# FT2232.net
KiCad netlist of a schematic drawn in Altium Designer
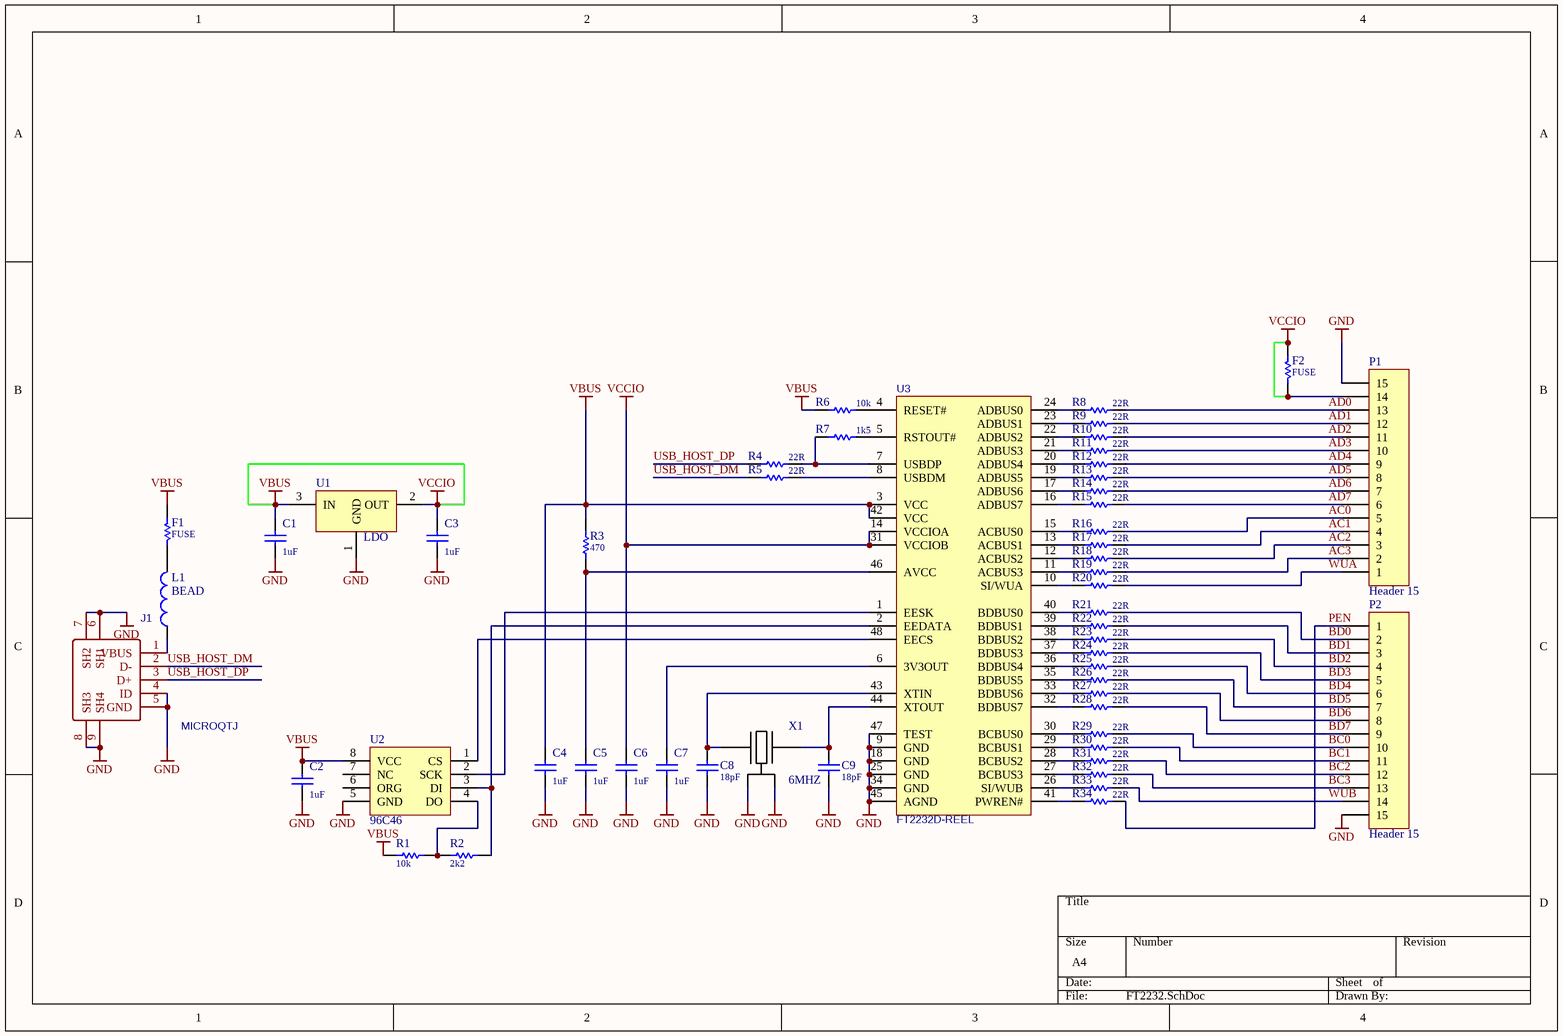
[diagram p0: FT2232.SchDoc]

(export (version "E")
  (design (tool "Eeschema 10.0.6"))
  (components
    (comp (ref "C1")
      (value "1uF")
      (footprint "C0603")
      (description "1uF 25V X7R 0603")
      (fields (field (name "LCSC PART NUMBER") "C59302"))
      (libsource (lib "Miscellaneous Devices") (part "CAP"))
    )
    (comp (ref "C2")
      (value "1uF")
      (footprint "C0603")
      (description "1uF 25V X7R 0603")
      (fields (field (name "LCSC PART NUMBER") "C59302"))
      (libsource (lib "Miscellaneous Devices") (part "CAP"))
    )
    (comp (ref "C3")
      (value "1uF")
      (footprint "C0603")
      (description "1uF 25V X7R 0603")
      (fields (field (name "LCSC PART NUMBER") "C59302"))
      (libsource (lib "Miscellaneous Devices") (part "CAP"))
    )
    (comp (ref "C4")
      (value "1uF")
      (footprint "C0603")
      (description "1uF 25V X7R 0603")
      (fields (field (name "LCSC PART NUMBER") "C59302"))
      (libsource (lib "Miscellaneous Devices") (part "CAP"))
    )
    (comp (ref "C5")
      (value "1uF")
      (footprint "C0603")
      (description "1uF 25V X7R 0603")
      (fields (field (name "LCSC PART NUMBER") "C59302"))
      (libsource (lib "Miscellaneous Devices") (part "CAP"))
    )
    (comp (ref "C6")
      (value "1uF")
      (footprint "C0603")
      (description "1uF 25V X7R 0603")
      (fields (field (name "LCSC PART NUMBER") "C59302"))
      (libsource (lib "Miscellaneous Devices") (part "CAP"))
    )
    (comp (ref "C7")
      (value "1uF")
      (footprint "C0603")
      (description "1uF 25V X7R 0603")
      (fields (field (name "LCSC PART NUMBER") "C59302"))
      (libsource (lib "Miscellaneous Devices") (part "CAP"))
    )
    (comp (ref "C8")
      (value "18pF")
      (footprint "C0402")
      (description "18pF 50V 0402")
      (fields (field (name "LCSC PART NUMBER") "C33149"))
      (libsource (lib "Miscellaneous Devices") (part "CAP"))
    )
    (comp (ref "C9")
      (value "18pF")
      (footprint "C0402")
      (description "18pF 50V 0402")
      (fields (field (name "LCSC PART NUMBER") "C33149"))
      (libsource (lib "Miscellaneous Devices") (part "CAP"))
    )
    (comp (ref "F1")
      (value "FUSE")
      (footprint "R1206")
      (libsource (lib "Miscellaneous Devices") (part "RES"))
    )
    (comp (ref "F2")
      (value "FUSE")
      (footprint "R1206")
      (libsource (lib "Miscellaneous Devices") (part "RES"))
    )
    (comp (ref "J1")
      (value "MICROQTJ")
      (footprint "MICRO-USB-SMD_MICROQTJ")
      (fields
        (field (name "BOM_SUPPLIER PART") "C404968")
        (field (name "BOM_MANUFACTURER PART") "MicroQTJ")
        (field (name "CONTRIBUTOR") "LCSC")
      )
      (libsource (lib "altium-import") (part "root_0_MICROQTJ_"))
    )
    (comp (ref "L1")
      (value "BEAD")
      (footprint "L0402")
      (description "INDUCTOR FERRITE BEAD 200mA 1 650mΩ 0402")
      (fields (field (name "LCSC PART NUMBER") "C92615"))
      (libsource (lib "Miscellaneous Devices") (part "BLM18AG601SN1D"))
    )
    (comp (ref "P1")
      (value "Header 15")
      (footprint "HDR1X15")
      (description "Header, 15-Pin")
      (fields (field (name "PUBLISHER") "Altium Limited"))
      (libsource (lib "Miscellaneous Connectors") (part "Header 15"))
    )
    (comp (ref "P2")
      (value "Header 15")
      (footprint "HDR1X15")
      (description "Header, 15-Pin")
      (fields (field (name "PUBLISHER") "Altium Limited"))
      (libsource (lib "") (part "Header 15_1"))
    )
    (comp (ref "R1")
      (value "10k")
      (footprint "R0603")
      (description "10k 0603")
      (libsource (lib "Miscellaneous Devices") (part "RES"))
    )
    (comp (ref "R2") (value "2k2") (footprint "R0603") (libsource (lib "Miscellaneous Devices") (part "RES")))
    (comp (ref "R3") (value "470") (footprint "R0603") (libsource (lib "Miscellaneous Devices") (part "RES")))
    (comp (ref "R4")
      (value "22R")
      (footprint "R0603")
      (description "22R 5% 0603")
      (libsource (lib "Miscellaneous Devices") (part "RES"))
    )
    (comp (ref "R5")
      (value "22R")
      (footprint "R0603")
      (description "22R 5% 0603")
      (libsource (lib "Miscellaneous Devices") (part "RES"))
    )
    (comp (ref "R6")
      (value "10k")
      (footprint "R0603")
      (description "10k 0603")
      (libsource (lib "Miscellaneous Devices") (part "RES"))
    )
    (comp (ref "R7")
      (value "1k5")
      (footprint "R0603")
      (description "10k 0603")
      (libsource (lib "Miscellaneous Devices") (part "RES"))
    )
    (comp (ref "R8")
      (value "22R")
      (footprint "R0603")
      (description "22R 5% 0603")
      (libsource (lib "Miscellaneous Devices") (part "RES"))
    )
    (comp (ref "R9")
      (value "22R")
      (footprint "R0603")
      (description "22R 5% 0603")
      (libsource (lib "Miscellaneous Devices") (part "RES"))
    )
    (comp (ref "R10")
      (value "22R")
      (footprint "R0603")
      (description "22R 5% 0603")
      (libsource (lib "Miscellaneous Devices") (part "RES"))
    )
    (comp (ref "R11")
      (value "22R")
      (footprint "R0603")
      (description "22R 5% 0603")
      (libsource (lib "Miscellaneous Devices") (part "RES"))
    )
    (comp (ref "R12")
      (value "22R")
      (footprint "R0603")
      (description "22R 5% 0603")
      (libsource (lib "Miscellaneous Devices") (part "RES"))
    )
    (comp (ref "R13")
      (value "22R")
      (footprint "R0603")
      (description "22R 5% 0603")
      (libsource (lib "Miscellaneous Devices") (part "RES"))
    )
    (comp (ref "R14")
      (value "22R")
      (footprint "R0603")
      (description "22R 5% 0603")
      (libsource (lib "Miscellaneous Devices") (part "RES"))
    )
    (comp (ref "R15")
      (value "22R")
      (footprint "R0603")
      (description "22R 5% 0603")
      (libsource (lib "Miscellaneous Devices") (part "RES"))
    )
    (comp (ref "R16")
      (value "22R")
      (footprint "R0603")
      (description "22R 5% 0603")
      (libsource (lib "Miscellaneous Devices") (part "RES"))
    )
    (comp (ref "R17")
      (value "22R")
      (footprint "R0603")
      (description "22R 5% 0603")
      (libsource (lib "Miscellaneous Devices") (part "RES"))
    )
    (comp (ref "R18")
      (value "22R")
      (footprint "R0603")
      (description "22R 5% 0603")
      (libsource (lib "Miscellaneous Devices") (part "RES"))
    )
    (comp (ref "R19")
      (value "22R")
      (footprint "R0603")
      (description "22R 5% 0603")
      (libsource (lib "Miscellaneous Devices") (part "RES"))
    )
    (comp (ref "R20")
      (value "22R")
      (footprint "R0603")
      (description "22R 5% 0603")
      (libsource (lib "Miscellaneous Devices") (part "RES"))
    )
    (comp (ref "R21")
      (value "22R")
      (footprint "R0603")
      (description "22R 5% 0603")
      (libsource (lib "Miscellaneous Devices") (part "RES"))
    )
    (comp (ref "R22")
      (value "22R")
      (footprint "R0603")
      (description "22R 5% 0603")
      (libsource (lib "Miscellaneous Devices") (part "RES"))
    )
    (comp (ref "R23")
      (value "22R")
      (footprint "R0603")
      (description "22R 5% 0603")
      (libsource (lib "Miscellaneous Devices") (part "RES"))
    )
    (comp (ref "R24")
      (value "22R")
      (footprint "R0603")
      (description "22R 5% 0603")
      (libsource (lib "Miscellaneous Devices") (part "RES"))
    )
    (comp (ref "R25")
      (value "22R")
      (footprint "R0603")
      (description "22R 5% 0603")
      (libsource (lib "Miscellaneous Devices") (part "RES"))
    )
    (comp (ref "R26")
      (value "22R")
      (footprint "R0603")
      (description "22R 5% 0603")
      (libsource (lib "Miscellaneous Devices") (part "RES"))
    )
    (comp (ref "R27")
      (value "22R")
      (footprint "R0603")
      (description "22R 5% 0603")
      (libsource (lib "Miscellaneous Devices") (part "RES"))
    )
    (comp (ref "R28")
      (value "22R")
      (footprint "R0603")
      (description "22R 5% 0603")
      (libsource (lib "Miscellaneous Devices") (part "RES"))
    )
    (comp (ref "R29")
      (value "22R")
      (footprint "R0603")
      (description "22R 5% 0603")
      (libsource (lib "Miscellaneous Devices") (part "RES"))
    )
    (comp (ref "R30")
      (value "22R")
      (footprint "R0603")
      (description "22R 5% 0603")
      (libsource (lib "Miscellaneous Devices") (part "RES"))
    )
    (comp (ref "R31")
      (value "22R")
      (footprint "R0603")
      (description "22R 5% 0603")
      (libsource (lib "Miscellaneous Devices") (part "RES"))
    )
    (comp (ref "R32")
      (value "22R")
      (footprint "R0603")
      (description "22R 5% 0603")
      (libsource (lib "Miscellaneous Devices") (part "RES"))
    )
    (comp (ref "R33")
      (value "22R")
      (footprint "R0603")
      (description "22R 5% 0603")
      (libsource (lib "Miscellaneous Devices") (part "RES"))
    )
    (comp (ref "R34")
      (value "22R")
      (footprint "R0603")
      (description "22R 5% 0603")
      (libsource (lib "Miscellaneous Devices") (part "RES"))
    )
    (comp (ref "U1")
      (value "LDO")
      (footprint "TO-252AA (DPAK)")
      (libsource (lib "Miscellaneous Devices") (part "NCP51460SN33T1G"))
    )
    (comp (ref "U2") (value "96C46") (footprint "MSOP8") (libsource (lib "Schlib1") (part "Component_2")))
    (comp (ref "U3")
      (value "FT2232D-REEL")
      (footprint "LQFP-48_L7.0-W7.0-P0.50-LS9.0-BL")
      (fields (field (name "BOM_SUPPLIER PART") "C428116") (field (name "CONTRIBUTOR") "LCSC"))
      (libsource (lib "Schlib1") (part "FT2232D-REEL"))
    )
    (comp (ref "X1")
      (value "6MHZ")
      (footprint "CRYSTAL_3.2x2.5mm")
      (description "CRYSTAL 6MHZ 10PF SMD")
      (fields (field (name "LCSC PART NUMBER") "C70565"))
      (libsource (lib "Miscellaneous Devices") (part "CRYSTAL 12MHZ 3.20mm x 2.50mm"))
    )
  )
  (nets
    (net (code "1") (name "/AC0") (class "Default")
      (node (ref "P1") (pin "5") (pinfunction "5_5") (pintype "passive"))
      (node (ref "R16") (pin "1") (pinfunction "1_1") (pintype "passive"))
    )
    (net (code "2") (name "/AC1") (class "Default")
      (node (ref "P1") (pin "4") (pinfunction "4_4") (pintype "passive"))
      (node (ref "R17") (pin "1") (pinfunction "1_1") (pintype "passive"))
    )
    (net (code "3") (name "/AC2") (class "Default")
      (node (ref "P1") (pin "3") (pinfunction "3_3") (pintype "passive"))
      (node (ref "R18") (pin "1") (pinfunction "1_1") (pintype "passive"))
    )
    (net (code "4") (name "/AC3") (class "Default")
      (node (ref "P1") (pin "2") (pinfunction "2_2") (pintype "passive"))
      (node (ref "R19") (pin "1") (pinfunction "1_1") (pintype "passive"))
    )
    (net (code "5") (name "/AD0") (class "Default")
      (node (ref "P1") (pin "13") (pinfunction "13_13") (pintype "passive"))
      (node (ref "R8") (pin "1") (pinfunction "1_1") (pintype "passive"))
    )
    (net (code "6") (name "/AD1") (class "Default")
      (node (ref "P1") (pin "12") (pinfunction "12_12") (pintype "passive"))
      (node (ref "R9") (pin "1") (pinfunction "1_1") (pintype "passive"))
    )
    (net (code "7") (name "/AD2") (class "Default")
      (node (ref "P1") (pin "11") (pinfunction "11_11") (pintype "passive"))
      (node (ref "R10") (pin "1") (pinfunction "1_1") (pintype "passive"))
    )
    (net (code "8") (name "/AD3") (class "Default")
      (node (ref "P1") (pin "10") (pinfunction "10_10") (pintype "passive"))
      (node (ref "R11") (pin "1") (pinfunction "1_1") (pintype "passive"))
    )
    (net (code "9") (name "/AD4") (class "Default")
      (node (ref "P1") (pin "9") (pinfunction "9_9") (pintype "passive"))
      (node (ref "R12") (pin "1") (pinfunction "1_1") (pintype "passive"))
    )
    (net (code "10") (name "/AD5") (class "Default")
      (node (ref "P1") (pin "8") (pinfunction "8_8") (pintype "passive"))
      (node (ref "R13") (pin "1") (pinfunction "1_1") (pintype "passive"))
    )
    (net (code "11") (name "/AD6") (class "Default")
      (node (ref "P1") (pin "7") (pinfunction "7_7") (pintype "passive"))
      (node (ref "R14") (pin "1") (pinfunction "1_1") (pintype "passive"))
    )
    (net (code "12") (name "/AD7") (class "Default")
      (node (ref "P1") (pin "6") (pinfunction "6_6") (pintype "passive"))
      (node (ref "R15") (pin "1") (pinfunction "1_1") (pintype "passive"))
    )
    (net (code "13") (name "/BC0") (class "Default")
      (node (ref "P2") (pin "10") (pinfunction "10_10") (pintype "passive"))
      (node (ref "R29") (pin "1") (pinfunction "1_1") (pintype "passive"))
    )
    (net (code "14") (name "/BC1") (class "Default")
      (node (ref "P2") (pin "11") (pinfunction "11_11") (pintype "passive"))
      (node (ref "R30") (pin "1") (pinfunction "1_1") (pintype "passive"))
    )
    (net (code "15") (name "/BC2") (class "Default")
      (node (ref "P2") (pin "12") (pinfunction "12_12") (pintype "passive"))
      (node (ref "R31") (pin "1") (pinfunction "1_1") (pintype "passive"))
    )
    (net (code "16") (name "/BC3") (class "Default")
      (node (ref "P2") (pin "13") (pinfunction "13_13") (pintype "passive"))
      (node (ref "R32") (pin "1") (pinfunction "1_1") (pintype "passive"))
    )
    (net (code "17") (name "/BD0") (class "Default")
      (node (ref "P2") (pin "2") (pinfunction "2_2") (pintype "passive"))
      (node (ref "R21") (pin "1") (pinfunction "1_1") (pintype "passive"))
    )
    (net (code "18") (name "/BD1") (class "Default")
      (node (ref "P2") (pin "3") (pinfunction "3_3") (pintype "passive"))
      (node (ref "R22") (pin "1") (pinfunction "1_1") (pintype "passive"))
    )
    (net (code "19") (name "/BD2") (class "Default")
      (node (ref "P2") (pin "4") (pinfunction "4_4") (pintype "passive"))
      (node (ref "R23") (pin "1") (pinfunction "1_1") (pintype "passive"))
    )
    (net (code "20") (name "/BD3") (class "Default")
      (node (ref "P2") (pin "5") (pinfunction "5_5") (pintype "passive"))
      (node (ref "R24") (pin "1") (pinfunction "1_1") (pintype "passive"))
    )
    (net (code "21") (name "/BD4") (class "Default")
      (node (ref "P2") (pin "6") (pinfunction "6_6") (pintype "passive"))
      (node (ref "R25") (pin "1") (pinfunction "1_1") (pintype "passive"))
    )
    (net (code "22") (name "/BD5") (class "Default")
      (node (ref "P2") (pin "7") (pinfunction "7_7") (pintype "passive"))
      (node (ref "R26") (pin "1") (pinfunction "1_1") (pintype "passive"))
    )
    (net (code "23") (name "/BD6") (class "Default")
      (node (ref "P2") (pin "8") (pinfunction "8_8") (pintype "passive"))
      (node (ref "R27") (pin "1") (pinfunction "1_1") (pintype "passive"))
    )
    (net (code "24") (name "/BD7") (class "Default")
      (node (ref "P2") (pin "9") (pinfunction "9_9") (pintype "passive"))
      (node (ref "R28") (pin "1") (pinfunction "1_1") (pintype "passive"))
    )
    (net (code "25") (name "/PEN") (class "Default")
      (node (ref "P2") (pin "1") (pinfunction "1_1") (pintype "passive"))
      (node (ref "R34") (pin "1") (pinfunction "1_1") (pintype "passive"))
    )
    (net (code "26") (name "/USB_HOST_DM") (class "Default")
      (node (ref "J1") (pin "2") (pinfunction "D-_2") (pintype "passive"))
      (node (ref "R5") (pin "2") (pinfunction "2_2") (pintype "passive"))
    )
    (net (code "27") (name "/USB_HOST_DP") (class "Default")
      (node (ref "J1") (pin "3") (pinfunction "D+_3") (pintype "passive"))
      (node (ref "R4") (pin "2") (pinfunction "2_2") (pintype "passive"))
    )
    (net (code "28") (name "/WUA") (class "Default")
      (node (ref "P1") (pin "1") (pinfunction "1_1") (pintype "passive"))
      (node (ref "R20") (pin "1") (pinfunction "1_1") (pintype "passive"))
    )
    (net (code "29") (name "/WUB") (class "Default")
      (node (ref "P2") (pin "14") (pinfunction "14_14") (pintype "passive"))
      (node (ref "R33") (pin "1") (pinfunction "1_1") (pintype "passive"))
    )
    (net (code "30") (name "GND") (class "Default")
      (node (ref "C1") (pin "1") (pinfunction "1_1") (pintype "passive"))
      (node (ref "C2") (pin "1") (pinfunction "1_1") (pintype "passive"))
      (node (ref "C3") (pin "1") (pinfunction "1_1") (pintype "passive"))
      (node (ref "C4") (pin "1") (pinfunction "1_1") (pintype "passive"))
      (node (ref "C5") (pin "1") (pinfunction "1_1") (pintype "passive"))
      (node (ref "C6") (pin "1") (pinfunction "1_1") (pintype "passive"))
      (node (ref "C7") (pin "1") (pinfunction "1_1") (pintype "passive"))
      (node (ref "C8") (pin "1") (pinfunction "1_1") (pintype "passive"))
      (node (ref "C9") (pin "1") (pinfunction "1_1") (pintype "passive"))
      (node (ref "J1") (pin "4") (pinfunction "ID_4") (pintype "passive"))
      (node (ref "J1") (pin "5") (pinfunction "GND_5") (pintype "passive"))
      (node (ref "J1") (pin "6") (pinfunction "SH1_6") (pintype "passive"))
      (node (ref "J1") (pin "7") (pinfunction "SH2_7") (pintype "passive"))
      (node (ref "J1") (pin "8") (pinfunction "SH3_8") (pintype "passive"))
      (node (ref "J1") (pin "9") (pinfunction "SH4_9") (pintype "passive"))
      (node (ref "P1") (pin "15") (pinfunction "15_15") (pintype "passive"))
      (node (ref "P2") (pin "15") (pinfunction "15_15") (pintype "passive"))
      (node (ref "U1") (pin "1") (pinfunction "GND_1") (pintype "passive"))
      (node (ref "U2") (pin "5") (pinfunction "GND_5") (pintype "passive"))
      (node (ref "U3") (pin "18") (pinfunction "GND_18") (pintype "passive"))
      (node (ref "U3") (pin "25") (pinfunction "GND_25") (pintype "passive"))
      (node (ref "U3") (pin "34") (pinfunction "GND_34") (pintype "passive"))
      (node (ref "U3") (pin "45") (pinfunction "AGND_45") (pintype "passive"))
      (node (ref "U3") (pin "47") (pinfunction "TEST_47") (pintype "passive"))
      (node (ref "U3") (pin "9") (pinfunction "GND_9") (pintype "passive"))
      (node (ref "X1") (pin "2") (pinfunction "GND_2") (pintype "passive"))
      (node (ref "X1") (pin "4") (pinfunction "GND_4") (pintype "passive"))
    )
    (net (code "31") (name "Net-(F1-Pad1)") (class "Default")
      (node (ref "F1") (pin "1") (pinfunction "1_1") (pintype "passive"))
      (node (ref "L1") (pin "1") (pinfunction "1_1") (pintype "passive"))
    )
    (net (code "32") (name "Net-(J1-VBUS)") (class "Default")
      (node (ref "J1") (pin "1") (pinfunction "VBUS_1") (pintype "passive"))
      (node (ref "L1") (pin "2") (pinfunction "2_2") (pintype "passive"))
    )
    (net (code "33") (name "Net-(U2-CS)") (class "Default")
      (node (ref "U2") (pin "1") (pinfunction "CS_1") (pintype "passive"))
      (node (ref "U3") (pin "48") (pinfunction "EECS_48") (pintype "passive"))
    )
    (net (code "34") (name "Net-(U2-DI)") (class "Default")
      (node (ref "R2") (pin "1") (pinfunction "1_1") (pintype "passive"))
      (node (ref "U2") (pin "3") (pinfunction "DI_3") (pintype "passive"))
      (node (ref "U3") (pin "2") (pinfunction "EEDATA_2") (pintype "passive"))
    )
    (net (code "35") (name "Net-(U2-DO)") (class "Default")
      (node (ref "R1") (pin "1") (pinfunction "1_1") (pintype "passive"))
      (node (ref "R2") (pin "2") (pinfunction "2_2") (pintype "passive"))
      (node (ref "U2") (pin "4") (pinfunction "DO_4") (pintype "passive"))
    )
    (net (code "36") (name "Net-(U2-SCK)") (class "Default")
      (node (ref "U2") (pin "2") (pinfunction "SCK_2") (pintype "passive"))
      (node (ref "U3") (pin "1") (pinfunction "EESK_1") (pintype "passive"))
    )
    (net (code "37") (name "Net-(U3-3V3OUT)") (class "Default")
      (node (ref "C7") (pin "2") (pinfunction "2_2") (pintype "passive"))
      (node (ref "U3") (pin "6") (pinfunction "3V3OUT_6") (pintype "passive"))
    )
    (net (code "38") (name "Net-(U3-ACBUS0)") (class "Default")
      (node (ref "R16") (pin "2") (pinfunction "2_2") (pintype "passive"))
      (node (ref "U3") (pin "15") (pinfunction "ACBUS0_15") (pintype "passive"))
    )
    (net (code "39") (name "Net-(U3-ACBUS1)") (class "Default")
      (node (ref "R17") (pin "2") (pinfunction "2_2") (pintype "passive"))
      (node (ref "U3") (pin "13") (pinfunction "ACBUS1_13") (pintype "passive"))
    )
    (net (code "40") (name "Net-(U3-ACBUS2)") (class "Default")
      (node (ref "R18") (pin "2") (pinfunction "2_2") (pintype "passive"))
      (node (ref "U3") (pin "12") (pinfunction "ACBUS2_12") (pintype "passive"))
    )
    (net (code "41") (name "Net-(U3-ACBUS3)") (class "Default")
      (node (ref "R19") (pin "2") (pinfunction "2_2") (pintype "passive"))
      (node (ref "U3") (pin "11") (pinfunction "ACBUS3_11") (pintype "passive"))
    )
    (net (code "42") (name "Net-(U3-ADBUS0)") (class "Default")
      (node (ref "R8") (pin "2") (pinfunction "2_2") (pintype "passive"))
      (node (ref "U3") (pin "24") (pinfunction "ADBUS0_24") (pintype "passive"))
    )
    (net (code "43") (name "Net-(U3-ADBUS1)") (class "Default")
      (node (ref "R9") (pin "2") (pinfunction "2_2") (pintype "passive"))
      (node (ref "U3") (pin "23") (pinfunction "ADBUS1_23") (pintype "passive"))
    )
    (net (code "44") (name "Net-(U3-ADBUS2)") (class "Default")
      (node (ref "R10") (pin "2") (pinfunction "2_2") (pintype "passive"))
      (node (ref "U3") (pin "22") (pinfunction "ADBUS2_22") (pintype "passive"))
    )
    (net (code "45") (name "Net-(U3-ADBUS3)") (class "Default")
      (node (ref "R11") (pin "2") (pinfunction "2_2") (pintype "passive"))
      (node (ref "U3") (pin "21") (pinfunction "ADBUS3_21") (pintype "passive"))
    )
    (net (code "46") (name "Net-(U3-ADBUS4)") (class "Default")
      (node (ref "R12") (pin "2") (pinfunction "2_2") (pintype "passive"))
      (node (ref "U3") (pin "20") (pinfunction "ADBUS4_20") (pintype "passive"))
    )
    (net (code "47") (name "Net-(U3-ADBUS5)") (class "Default")
      (node (ref "R13") (pin "2") (pinfunction "2_2") (pintype "passive"))
      (node (ref "U3") (pin "19") (pinfunction "ADBUS5_19") (pintype "passive"))
    )
    (net (code "48") (name "Net-(U3-ADBUS6)") (class "Default")
      (node (ref "R14") (pin "2") (pinfunction "2_2") (pintype "passive"))
      (node (ref "U3") (pin "17") (pinfunction "ADBUS6_17") (pintype "passive"))
    )
    (net (code "49") (name "Net-(U3-ADBUS7)") (class "Default")
      (node (ref "R15") (pin "2") (pinfunction "2_2") (pintype "passive"))
      (node (ref "U3") (pin "16") (pinfunction "ADBUS7_16") (pintype "passive"))
    )
    (net (code "50") (name "Net-(U3-AVCC)") (class "Default")
      (node (ref "C5") (pin "2") (pinfunction "2_2") (pintype "passive"))
      (node (ref "R3") (pin "2") (pinfunction "2_2") (pintype "passive"))
      (node (ref "U3") (pin "46") (pinfunction "AVCC_46") (pintype "passive"))
    )
    (net (code "51") (name "Net-(U3-BCBUS0)") (class "Default")
      (node (ref "R29") (pin "2") (pinfunction "2_2") (pintype "passive"))
      (node (ref "U3") (pin "30") (pinfunction "BCBUS0_30") (pintype "passive"))
    )
    (net (code "52") (name "Net-(U3-BCBUS1)") (class "Default")
      (node (ref "R30") (pin "2") (pinfunction "2_2") (pintype "passive"))
      (node (ref "U3") (pin "29") (pinfunction "BCBUS1_29") (pintype "passive"))
    )
    (net (code "53") (name "Net-(U3-BCBUS2)") (class "Default")
      (node (ref "R31") (pin "2") (pinfunction "2_2") (pintype "passive"))
      (node (ref "U3") (pin "28") (pinfunction "BCBUS2_28") (pintype "passive"))
    )
    (net (code "54") (name "Net-(U3-BCBUS3)") (class "Default")
      (node (ref "R32") (pin "2") (pinfunction "2_2") (pintype "passive"))
      (node (ref "U3") (pin "27") (pinfunction "BCBUS3_27") (pintype "passive"))
    )
    (net (code "55") (name "Net-(U3-BDBUS0)") (class "Default")
      (node (ref "R21") (pin "2") (pinfunction "2_2") (pintype "passive"))
      (node (ref "U3") (pin "40") (pinfunction "BDBUS0_40") (pintype "passive"))
    )
    (net (code "56") (name "Net-(U3-BDBUS1)") (class "Default")
      (node (ref "R22") (pin "2") (pinfunction "2_2") (pintype "passive"))
      (node (ref "U3") (pin "39") (pinfunction "BDBUS1_39") (pintype "passive"))
    )
    (net (code "57") (name "Net-(U3-BDBUS2)") (class "Default")
      (node (ref "R23") (pin "2") (pinfunction "2_2") (pintype "passive"))
      (node (ref "U3") (pin "38") (pinfunction "BDBUS2_38") (pintype "passive"))
    )
    (net (code "58") (name "Net-(U3-BDBUS3)") (class "Default")
      (node (ref "R24") (pin "2") (pinfunction "2_2") (pintype "passive"))
      (node (ref "U3") (pin "37") (pinfunction "BDBUS3_37") (pintype "passive"))
    )
    (net (code "59") (name "Net-(U3-BDBUS4)") (class "Default")
      (node (ref "R25") (pin "2") (pinfunction "2_2") (pintype "passive"))
      (node (ref "U3") (pin "36") (pinfunction "BDBUS4_36") (pintype "passive"))
    )
    (net (code "60") (name "Net-(U3-BDBUS5)") (class "Default")
      (node (ref "R26") (pin "2") (pinfunction "2_2") (pintype "passive"))
      (node (ref "U3") (pin "35") (pinfunction "BDBUS5_35") (pintype "passive"))
    )
    (net (code "61") (name "Net-(U3-BDBUS6)") (class "Default")
      (node (ref "R27") (pin "2") (pinfunction "2_2") (pintype "passive"))
      (node (ref "U3") (pin "33") (pinfunction "BDBUS6_33") (pintype "passive"))
    )
    (net (code "62") (name "Net-(U3-BDBUS7)") (class "Default")
      (node (ref "R28") (pin "2") (pinfunction "2_2") (pintype "passive"))
      (node (ref "U3") (pin "32") (pinfunction "BDBUS7_32") (pintype "passive"))
    )
    (net (code "63") (name "Net-(U3-PWREN#)") (class "Default")
      (node (ref "R34") (pin "2") (pinfunction "2_2") (pintype "passive"))
      (node (ref "U3") (pin "41") (pinfunction "PWREN#_41") (pintype "passive"))
    )
    (net (code "64") (name "Net-(U3-RESET#)") (class "Default")
      (node (ref "R6") (pin "1") (pinfunction "1_1") (pintype "passive"))
      (node (ref "U3") (pin "4") (pinfunction "RESET#_4") (pintype "passive"))
    )
    (net (code "65") (name "Net-(U3-RSTOUT#)") (class "Default")
      (node (ref "R7") (pin "1") (pinfunction "1_1") (pintype "passive"))
      (node (ref "U3") (pin "5") (pinfunction "RSTOUT#_5") (pintype "passive"))
    )
    (net (code "66") (name "Net-(U3-SI{slash}WUA)") (class "Default")
      (node (ref "R20") (pin "2") (pinfunction "2_2") (pintype "passive"))
      (node (ref "U3") (pin "10") (pinfunction "SI/WUA_10") (pintype "passive"))
    )
    (net (code "67") (name "Net-(U3-SI{slash}WUB)") (class "Default")
      (node (ref "R33") (pin "2") (pinfunction "2_2") (pintype "passive"))
      (node (ref "U3") (pin "26") (pinfunction "SI/WUB_26") (pintype "passive"))
    )
    (net (code "68") (name "Net-(U3-USBDM)") (class "Default")
      (node (ref "R5") (pin "1") (pinfunction "1_1") (pintype "passive"))
      (node (ref "U3") (pin "8") (pinfunction "USBDM_8") (pintype "passive"))
    )
    (net (code "69") (name "Net-(U3-USBDP)") (class "Default")
      (node (ref "R4") (pin "1") (pinfunction "1_1") (pintype "passive"))
      (node (ref "R7") (pin "2") (pinfunction "2_2") (pintype "passive"))
      (node (ref "U3") (pin "7") (pinfunction "USBDP_7") (pintype "passive"))
    )
    (net (code "70") (name "Net-(U3-XTIN)") (class "Default")
      (node (ref "C8") (pin "2") (pinfunction "2_2") (pintype "passive"))
      (node (ref "U3") (pin "43") (pinfunction "XTIN_43") (pintype "passive"))
      (node (ref "X1") (pin "1") (pinfunction "X1_1") (pintype "passive"))
    )
    (net (code "71") (name "Net-(U3-XTOUT)") (class "Default")
      (node (ref "C9") (pin "2") (pinfunction "2_2") (pintype "passive"))
      (node (ref "U3") (pin "44") (pinfunction "XTOUT_44") (pintype "passive"))
      (node (ref "X1") (pin "3") (pinfunction "X2_3") (pintype "passive"))
    )
    (net (code "72") (name "VBUS") (class "Default")
      (node (ref "C1") (pin "2") (pinfunction "2_2") (pintype "passive"))
      (node (ref "C2") (pin "2") (pinfunction "2_2") (pintype "passive"))
      (node (ref "C3") (pin "2") (pinfunction "2_2") (pintype "passive"))
      (node (ref "C4") (pin "2") (pinfunction "2_2") (pintype "passive"))
      (node (ref "C6") (pin "2") (pinfunction "2_2") (pintype "passive"))
      (node (ref "F1") (pin "2") (pinfunction "2_2") (pintype "passive"))
      (node (ref "F2") (pin "1") (pinfunction "1_1") (pintype "passive"))
      (node (ref "F2") (pin "2") (pinfunction "2_2") (pintype "passive"))
      (node (ref "P1") (pin "14") (pinfunction "14_14") (pintype "passive"))
      (node (ref "R1") (pin "2") (pinfunction "2_2") (pintype "passive"))
      (node (ref "R3") (pin "1") (pinfunction "1_1") (pintype "passive"))
      (node (ref "R6") (pin "2") (pinfunction "2_2") (pintype "passive"))
      (node (ref "U1") (pin "2") (pinfunction "OUT_2") (pintype "passive"))
      (node (ref "U1") (pin "3") (pinfunction "IN_3") (pintype "passive"))
      (node (ref "U2") (pin "8") (pinfunction "VCC_8") (pintype "passive"))
      (node (ref "U3") (pin "14") (pinfunction "VCCIOA_14") (pintype "passive"))
      (node (ref "U3") (pin "3") (pinfunction "VCC_3") (pintype "passive"))
      (node (ref "U3") (pin "31") (pinfunction "VCCIOB_31") (pintype "passive"))
      (node (ref "U3") (pin "42") (pinfunction "VCC_42") (pintype "passive"))
    )
    (net (code "73") (name "unconnected-(U2-NC-Pad7)") (class "Default")
      (node (ref "U2") (pin "7") (pinfunction "NC_7") (pintype "passive"))
    )
    (net (code "74") (name "unconnected-(U2-ORG-Pad6)") (class "Default")
      (node (ref "U2") (pin "6") (pinfunction "ORG_6") (pintype "passive"))
    )
  )
)
